# rc2usb_led.net
KiCad netlist of a schematic drawn in EAGLE
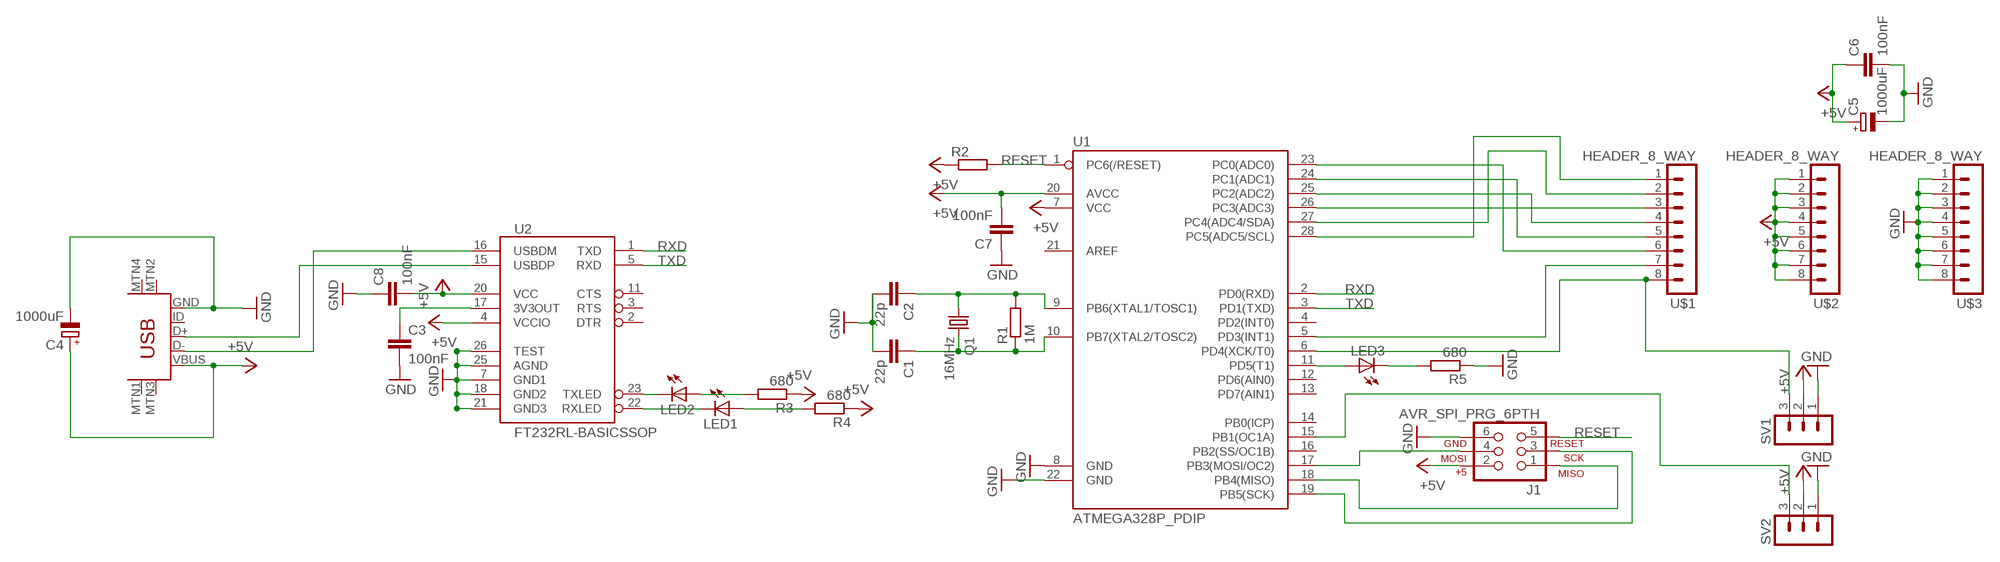
[diagram p0: schematic, sheet 1]

(export (version "E")
  (design (tool "Eeschema 10.0.6"))
  (components
    (comp (ref "C1")
      (value "22p")
      (footprint "eagle-import:C025-040X050")
      (libsource (lib "eagle-import") (part "resistor_C-EU025-040X050"))
    )
    (comp (ref "C2")
      (value "22p")
      (footprint "eagle-import:C025-040X050")
      (libsource (lib "eagle-import") (part "resistor_C-EU025-040X050"))
    )
    (comp (ref "C3")
      (value "100nF")
      (footprint "eagle-import:C025-030X050")
      (libsource (lib "eagle-import") (part "C-EU025-030X050"))
    )
    (comp (ref "C4")
      (value "1000uF")
      (footprint "eagle-import:E5-10,5")
      (libsource (lib "eagle-import") (part "CPOL-EUE5-10.5"))
    )
    (comp (ref "C5")
      (value "1000uF")
      (footprint "eagle-import:E5-10,5")
      (libsource (lib "eagle-import") (part "CPOL-EUE5-10.5"))
    )
    (comp (ref "C6")
      (value "100nF")
      (footprint "eagle-import:C025-030X050")
      (libsource (lib "eagle-import") (part "C-EU025-030X050"))
    )
    (comp (ref "C7")
      (value "100nF")
      (footprint "eagle-import:C025-030X050")
      (libsource (lib "eagle-import") (part "C-EU025-030X050"))
    )
    (comp (ref "C8")
      (value "100nF")
      (footprint "eagle-import:C025-030X050")
      (libsource (lib "eagle-import") (part "C-EU025-030X050"))
    )
    (comp (ref "J1")
      (value "AVR_SPI_PRG_6PTH")
      (footprint "eagle-import:2X3")
      (libsource (lib "eagle-import") (part "AVR_SPI_PRG_6PTH"))
    )
    (comp (ref "LED1")
      (value "LED5MM")
      (footprint "eagle-import:LED5MM")
      (libsource (lib "eagle-import") (part "LED5MM"))
    )
    (comp (ref "LED2")
      (value "LED5MM")
      (footprint "eagle-import:LED5MM")
      (libsource (lib "eagle-import") (part "LED5MM"))
    )
    (comp (ref "LED3")
      (value "LED5MM")
      (footprint "eagle-import:LED5MM")
      (libsource (lib "eagle-import") (part "LED5MM"))
    )
    (comp (ref "Q1")
      (value "16MHz")
      (footprint "eagle-import:HC49U70")
      (libsource (lib "eagle-import") (part "CRYSTALHC49U70"))
    )
    (comp (ref "R1")
      (value "1M")
      (footprint "eagle-import:0207_10")
      (libsource (lib "eagle-import") (part "R-EU_0207/10"))
    )
    (comp (ref "R2")
      (value "R-EU_0207/10")
      (footprint "eagle-import:0207_10")
      (libsource (lib "eagle-import") (part "R-EU_0207/10"))
    )
    (comp (ref "R3")
      (value "680")
      (footprint "eagle-import:0207_10")
      (libsource (lib "eagle-import") (part "R-EU_0207/10"))
    )
    (comp (ref "R4")
      (value "680")
      (footprint "eagle-import:0207_10")
      (libsource (lib "eagle-import") (part "R-EU_0207/10"))
    )
    (comp (ref "R5")
      (value "680")
      (footprint "eagle-import:0207_10")
      (libsource (lib "eagle-import") (part "R-EU_0207/10"))
    )
    (comp (ref "SV1")
      (value "MA03-1")
      (footprint "eagle-import:MA03-1")
      (libsource (lib "eagle-import") (part "MA03-1"))
    )
    (comp (ref "SV2")
      (value "MA03-1")
      (footprint "eagle-import:MA03-1")
      (libsource (lib "eagle-import") (part "MA03-1"))
    )
    (comp (ref "U$1")
      (value "HEADER_8_WAY")
      (footprint "eagle-import:HEADER_8_WAY")
      (libsource (lib "eagle-import") (part "HEADER_8_WAY"))
    )
    (comp (ref "U$2")
      (value "HEADER_8_WAY")
      (footprint "eagle-import:HEADER_8_WAY")
      (libsource (lib "eagle-import") (part "HEADER_8_WAY"))
    )
    (comp (ref "U$3")
      (value "HEADER_8_WAY")
      (footprint "eagle-import:HEADER_8_WAY")
      (libsource (lib "eagle-import") (part "HEADER_8_WAY"))
    )
    (comp (ref "U$4")
      (value "USB-MINIB-5PIN")
      (footprint "eagle-import:USB-MINIB")
      (libsource (lib "eagle-import") (part "USB-MINIB-5PIN"))
    )
    (comp (ref "U1")
      (value "ATMEGA328P_PDIP")
      (footprint "eagle-import:DIL28-3")
      (libsource (lib "eagle-import") (part "ATMEGA328P_PDIP"))
    )
    (comp (ref "U2")
      (value "FT232RL-BASICSSOP")
      (footprint "eagle-import:SSOP28DB")
      (libsource (lib "eagle-import") (part "FT232RL-BASICSSOP"))
    )
  )
  (nets
    (net (code "1") (name "+5V") (class "Default")
      (node (ref "C4") (pin "+") (pinfunction "+_+") (pintype "passive"))
      (node (ref "C5") (pin "+") (pinfunction "+_+") (pintype "passive"))
      (node (ref "C6") (pin "1") (pinfunction "1_1") (pintype "passive"))
      (node (ref "C7") (pin "2") (pinfunction "2_2") (pintype "passive"))
      (node (ref "C8") (pin "2") (pinfunction "2_2") (pintype "passive"))
      (node (ref "J1") (pin "2") (pinfunction "2_2") (pintype "passive"))
      (node (ref "R2") (pin "1") (pinfunction "1_1") (pintype "passive"))
      (node (ref "R3") (pin "1") (pinfunction "1_1") (pintype "passive"))
      (node (ref "R4") (pin "1") (pinfunction "1_1") (pintype "passive"))
      (node (ref "SV1") (pin "2") (pinfunction "2_2") (pintype "passive"))
      (node (ref "SV2") (pin "2") (pinfunction "2_2") (pintype "passive"))
      (node (ref "U$2") (pin "1") (pinfunction "1_1") (pintype "passive"))
      (node (ref "U$2") (pin "2") (pinfunction "2_2") (pintype "passive"))
      (node (ref "U$2") (pin "3") (pinfunction "3_3") (pintype "passive"))
      (node (ref "U$2") (pin "4") (pinfunction "4_4") (pintype "passive"))
      (node (ref "U$2") (pin "5") (pinfunction "5_5") (pintype "passive"))
      (node (ref "U$2") (pin "6") (pinfunction "6_6") (pintype "passive"))
      (node (ref "U$2") (pin "7") (pinfunction "7_7") (pintype "passive"))
      (node (ref "U$2") (pin "8") (pinfunction "8_8") (pintype "passive"))
      (node (ref "U$4") (pin "VBUS") (pinfunction "VBUS_VBUS") (pintype "bidirectional"))
      (node (ref "U1") (pin "20") (pinfunction "AVCC_20") (pintype "bidirectional"))
      (node (ref "U1") (pin "7") (pinfunction "VCC_7") (pintype "bidirectional"))
      (node (ref "U2") (pin "20") (pinfunction "VCC_20") (pintype "power_in"))
      (node (ref "U2") (pin "4") (pinfunction "VCCIO_4") (pintype "power_in"))
    )
    (net (code "2") (name "/RESET") (class "Default")
      (node (ref "J1") (pin "5") (pinfunction "5_5") (pintype "passive"))
      (node (ref "R2") (pin "2") (pinfunction "2_2") (pintype "passive"))
      (node (ref "U1") (pin "1") (pinfunction "PC6(/RESET)_1") (pintype "bidirectional"))
    )
    (net (code "3") (name "/RXD") (class "Default")
      (node (ref "U1") (pin "2") (pinfunction "PD0(RXD)_2") (pintype "bidirectional"))
      (node (ref "U2") (pin "1") (pinfunction "TXD_1") (pintype "output"))
    )
    (net (code "4") (name "/TXD") (class "Default")
      (node (ref "U1") (pin "3") (pinfunction "PD1(TXD)_3") (pintype "bidirectional"))
      (node (ref "U2") (pin "5") (pinfunction "RXD_5") (pintype "input"))
    )
    (net (code "5") (name "GND") (class "Default")
      (node (ref "C1") (pin "2") (pinfunction "2_2") (pintype "passive"))
      (node (ref "C2") (pin "2") (pinfunction "2_2") (pintype "passive"))
      (node (ref "C3") (pin "2") (pinfunction "2_2") (pintype "passive"))
      (node (ref "C4") (pin "-") (pinfunction "-_-") (pintype "passive"))
      (node (ref "C5") (pin "-") (pinfunction "-_-") (pintype "passive"))
      (node (ref "C6") (pin "2") (pinfunction "2_2") (pintype "passive"))
      (node (ref "C7") (pin "1") (pinfunction "1_1") (pintype "passive"))
      (node (ref "C8") (pin "1") (pinfunction "1_1") (pintype "passive"))
      (node (ref "J1") (pin "6") (pinfunction "6_6") (pintype "passive"))
      (node (ref "R5") (pin "1") (pinfunction "1_1") (pintype "passive"))
      (node (ref "SV1") (pin "1") (pinfunction "1_1") (pintype "passive"))
      (node (ref "SV2") (pin "1") (pinfunction "1_1") (pintype "passive"))
      (node (ref "U$3") (pin "1") (pinfunction "1_1") (pintype "passive"))
      (node (ref "U$3") (pin "2") (pinfunction "2_2") (pintype "passive"))
      (node (ref "U$3") (pin "3") (pinfunction "3_3") (pintype "passive"))
      (node (ref "U$3") (pin "4") (pinfunction "4_4") (pintype "passive"))
      (node (ref "U$3") (pin "5") (pinfunction "5_5") (pintype "passive"))
      (node (ref "U$3") (pin "6") (pinfunction "6_6") (pintype "passive"))
      (node (ref "U$3") (pin "7") (pinfunction "7_7") (pintype "passive"))
      (node (ref "U$3") (pin "8") (pinfunction "8_8") (pintype "passive"))
      (node (ref "U$4") (pin "GND") (pinfunction "GND_GND") (pintype "bidirectional"))
      (node (ref "U1") (pin "22") (pinfunction "GND_22") (pintype "bidirectional"))
      (node (ref "U1") (pin "8") (pinfunction "GND_8") (pintype "bidirectional"))
      (node (ref "U2") (pin "18") (pinfunction "GND2_18") (pintype "power_in"))
      (node (ref "U2") (pin "21") (pinfunction "GND3_21") (pintype "power_in"))
      (node (ref "U2") (pin "25") (pinfunction "AGND_25") (pintype "power_in"))
      (node (ref "U2") (pin "26") (pinfunction "TEST_26") (pintype "input"))
      (node (ref "U2") (pin "7") (pinfunction "GND1_7") (pintype "power_in"))
    )
    (net (code "6") (name "Net-(LED1-C)") (class "Default")
      (node (ref "LED1") (pin "K") (pinfunction "C_K") (pintype "passive"))
      (node (ref "U2") (pin "22") (pinfunction "RXLED_22") (pintype "bidirectional"))
    )
    (net (code "7") (name "Net-(LED1-PadA)") (class "Default")
      (node (ref "LED1") (pin "A") (pinfunction "A_A") (pintype "passive"))
      (node (ref "R4") (pin "2") (pinfunction "2_2") (pintype "passive"))
    )
    (net (code "8") (name "Net-(LED2-C)") (class "Default")
      (node (ref "LED2") (pin "K") (pinfunction "C_K") (pintype "passive"))
      (node (ref "U2") (pin "23") (pinfunction "TXLED_23") (pintype "bidirectional"))
    )
    (net (code "9") (name "Net-(LED2-PadA)") (class "Default")
      (node (ref "LED2") (pin "A") (pinfunction "A_A") (pintype "passive"))
      (node (ref "R3") (pin "2") (pinfunction "2_2") (pintype "passive"))
    )
    (net (code "10") (name "Net-(LED3-C)") (class "Default")
      (node (ref "LED3") (pin "K") (pinfunction "C_K") (pintype "passive"))
      (node (ref "R5") (pin "2") (pinfunction "2_2") (pintype "passive"))
    )
    (net (code "11") (name "Net-(U1-PB1(OC1A))") (class "Default")
      (node (ref "SV2") (pin "3") (pinfunction "3_3") (pintype "passive"))
      (node (ref "U1") (pin "15") (pinfunction "PB1(OC1A)_15") (pintype "bidirectional"))
    )
    (net (code "12") (name "Net-(U1-PB3(MOSI{slash}OC2))") (class "Default")
      (node (ref "J1") (pin "4") (pinfunction "4_4") (pintype "passive"))
      (node (ref "U1") (pin "17") (pinfunction "PB3(MOSI/OC2)_17") (pintype "bidirectional"))
    )
    (net (code "13") (name "Net-(U1-PB4(MISO))") (class "Default")
      (node (ref "J1") (pin "1") (pinfunction "1_1") (pintype "passive"))
      (node (ref "U1") (pin "18") (pinfunction "PB4(MISO)_18") (pintype "bidirectional"))
    )
    (net (code "14") (name "Net-(U1-PB5(SCK))") (class "Default")
      (node (ref "J1") (pin "3") (pinfunction "3_3") (pintype "passive"))
      (node (ref "U1") (pin "19") (pinfunction "PB5(SCK)_19") (pintype "bidirectional"))
    )
    (net (code "15") (name "Net-(U1-PB6(XTAL1{slash}TOSC1))") (class "Default")
      (node (ref "C2") (pin "1") (pinfunction "1_1") (pintype "passive"))
      (node (ref "Q1") (pin "1") (pinfunction "1_1") (pintype "passive"))
      (node (ref "R1") (pin "2") (pinfunction "2_2") (pintype "passive"))
      (node (ref "U1") (pin "9") (pinfunction "PB6(XTAL1/TOSC1)_9") (pintype "bidirectional"))
    )
    (net (code "16") (name "Net-(U1-PB7(XTAL2{slash}TOSC2))") (class "Default")
      (node (ref "C1") (pin "1") (pinfunction "1_1") (pintype "passive"))
      (node (ref "Q1") (pin "2") (pinfunction "2_2") (pintype "passive"))
      (node (ref "R1") (pin "1") (pinfunction "1_1") (pintype "passive"))
      (node (ref "U1") (pin "10") (pinfunction "PB7(XTAL2/TOSC2)_10") (pintype "bidirectional"))
    )
    (net (code "17") (name "Net-(U1-PC0(ADC0))") (class "Default")
      (node (ref "U$1") (pin "6") (pinfunction "6_6") (pintype "passive"))
      (node (ref "U1") (pin "23") (pinfunction "PC0(ADC0)_23") (pintype "bidirectional"))
    )
    (net (code "18") (name "Net-(U1-PC1(ADC1))") (class "Default")
      (node (ref "U$1") (pin "5") (pinfunction "5_5") (pintype "passive"))
      (node (ref "U1") (pin "24") (pinfunction "PC1(ADC1)_24") (pintype "bidirectional"))
    )
    (net (code "19") (name "Net-(U1-PC2(ADC2))") (class "Default")
      (node (ref "U$1") (pin "4") (pinfunction "4_4") (pintype "passive"))
      (node (ref "U1") (pin "25") (pinfunction "PC2(ADC2)_25") (pintype "bidirectional"))
    )
    (net (code "20") (name "Net-(U1-PC3(ADC3))") (class "Default")
      (node (ref "U$1") (pin "3") (pinfunction "3_3") (pintype "passive"))
      (node (ref "U1") (pin "26") (pinfunction "PC3(ADC3)_26") (pintype "bidirectional"))
    )
    (net (code "21") (name "Net-(U1-PC4(ADC4{slash}SDA))") (class "Default")
      (node (ref "U$1") (pin "2") (pinfunction "2_2") (pintype "passive"))
      (node (ref "U1") (pin "27") (pinfunction "PC4(ADC4/SDA)_27") (pintype "bidirectional"))
    )
    (net (code "22") (name "Net-(U1-PC5(ADC5{slash}SCL))") (class "Default")
      (node (ref "U$1") (pin "1") (pinfunction "1_1") (pintype "passive"))
      (node (ref "U1") (pin "28") (pinfunction "PC5(ADC5/SCL)_28") (pintype "bidirectional"))
    )
    (net (code "23") (name "Net-(U1-PD3(INT1))") (class "Default")
      (node (ref "U$1") (pin "7") (pinfunction "7_7") (pintype "passive"))
      (node (ref "U1") (pin "5") (pinfunction "PD3(INT1)_5") (pintype "bidirectional"))
    )
    (net (code "24") (name "Net-(U1-PD4(XCK{slash}T0))") (class "Default")
      (node (ref "SV1") (pin "3") (pinfunction "3_3") (pintype "passive"))
      (node (ref "U$1") (pin "8") (pinfunction "8_8") (pintype "passive"))
      (node (ref "U1") (pin "6") (pinfunction "PD4(XCK/T0)_6") (pintype "bidirectional"))
    )
    (net (code "25") (name "Net-(U1-PD5(T1))") (class "Default")
      (node (ref "LED3") (pin "A") (pinfunction "A_A") (pintype "passive"))
      (node (ref "U1") (pin "11") (pinfunction "PD5(T1)_11") (pintype "bidirectional"))
    )
    (net (code "26") (name "Net-(U2-3V3OUT)") (class "Default")
      (node (ref "C3") (pin "1") (pinfunction "1_1") (pintype "passive"))
      (node (ref "U2") (pin "17") (pinfunction "3V3OUT_17") (pintype "output"))
    )
    (net (code "27") (name "Net-(U2-USBDM)") (class "Default")
      (node (ref "U$4") (pin "D-") (pinfunction "D-_D-") (pintype "bidirectional"))
      (node (ref "U2") (pin "16") (pinfunction "USBDM_16") (pintype "bidirectional"))
    )
    (net (code "28") (name "Net-(U2-USBDP)") (class "Default")
      (node (ref "U$4") (pin "D+") (pinfunction "D+_D+") (pintype "bidirectional"))
      (node (ref "U2") (pin "15") (pinfunction "USBDP_15") (pintype "bidirectional"))
    )
    (net (code "29") (name "unconnected-(U$4-MTN1-PadMTN3)") (class "Default")
      (node (ref "U$4") (pin "MTN3") (pinfunction "MTN1_MTN3") (pintype "bidirectional"))
    )
    (net (code "30") (name "unconnected-(U$4-MTN2-PadMTN1)") (class "Default")
      (node (ref "U$4") (pin "MTN1") (pinfunction "MTN2_MTN1") (pintype "bidirectional"))
    )
    (net (code "31") (name "unconnected-(U$4-MTN3-PadMTN2)") (class "Default")
      (node (ref "U$4") (pin "MTN2") (pinfunction "MTN3_MTN2") (pintype "bidirectional"))
    )
    (net (code "32") (name "unconnected-(U$4-PadID)") (class "Default")
      (node (ref "U$4") (pin "ID") (pinfunction "ID_ID") (pintype "bidirectional"))
    )
    (net (code "33") (name "unconnected-(U$4-PadMTN4)") (class "Default")
      (node (ref "U$4") (pin "MTN4") (pinfunction "MTN4_MTN4") (pintype "bidirectional"))
    )
    (net (code "34") (name "unconnected-(U1-AREF-Pad21)") (class "Default")
      (node (ref "U1") (pin "21") (pinfunction "AREF_21") (pintype "bidirectional"))
    )
    (net (code "35") (name "unconnected-(U1-PB0(ICP)-Pad14)") (class "Default")
      (node (ref "U1") (pin "14") (pinfunction "PB0(ICP)_14") (pintype "bidirectional"))
    )
    (net (code "36") (name "unconnected-(U1-PB2(SS{slash}OC1B)-Pad16)") (class "Default")
      (node (ref "U1") (pin "16") (pinfunction "PB2(SS/OC1B)_16") (pintype "bidirectional"))
    )
    (net (code "37") (name "unconnected-(U1-PD2(INT0)-Pad4)") (class "Default")
      (node (ref "U1") (pin "4") (pinfunction "PD2(INT0)_4") (pintype "bidirectional"))
    )
    (net (code "38") (name "unconnected-(U1-PD6(AIN0)-Pad12)") (class "Default")
      (node (ref "U1") (pin "12") (pinfunction "PD6(AIN0)_12") (pintype "bidirectional"))
    )
    (net (code "39") (name "unconnected-(U1-PD7(AIN1)-Pad13)") (class "Default")
      (node (ref "U1") (pin "13") (pinfunction "PD7(AIN1)_13") (pintype "bidirectional"))
    )
    (net (code "40") (name "unconnected-(U2-CTS-Pad11)") (class "Default")
      (node (ref "U2") (pin "11") (pinfunction "CTS_11") (pintype "bidirectional"))
    )
    (net (code "41") (name "unconnected-(U2-DTR-Pad2)") (class "Default")
      (node (ref "U2") (pin "2") (pinfunction "DTR_2") (pintype "bidirectional"))
    )
    (net (code "42") (name "unconnected-(U2-RTS-Pad3)") (class "Default")
      (node (ref "U2") (pin "3") (pinfunction "RTS_3") (pintype "bidirectional"))
    )
  )
)
